# voltage_sensor_v1_2_RJ45.net
KiCad netlist of a schematic drawn in EAGLE
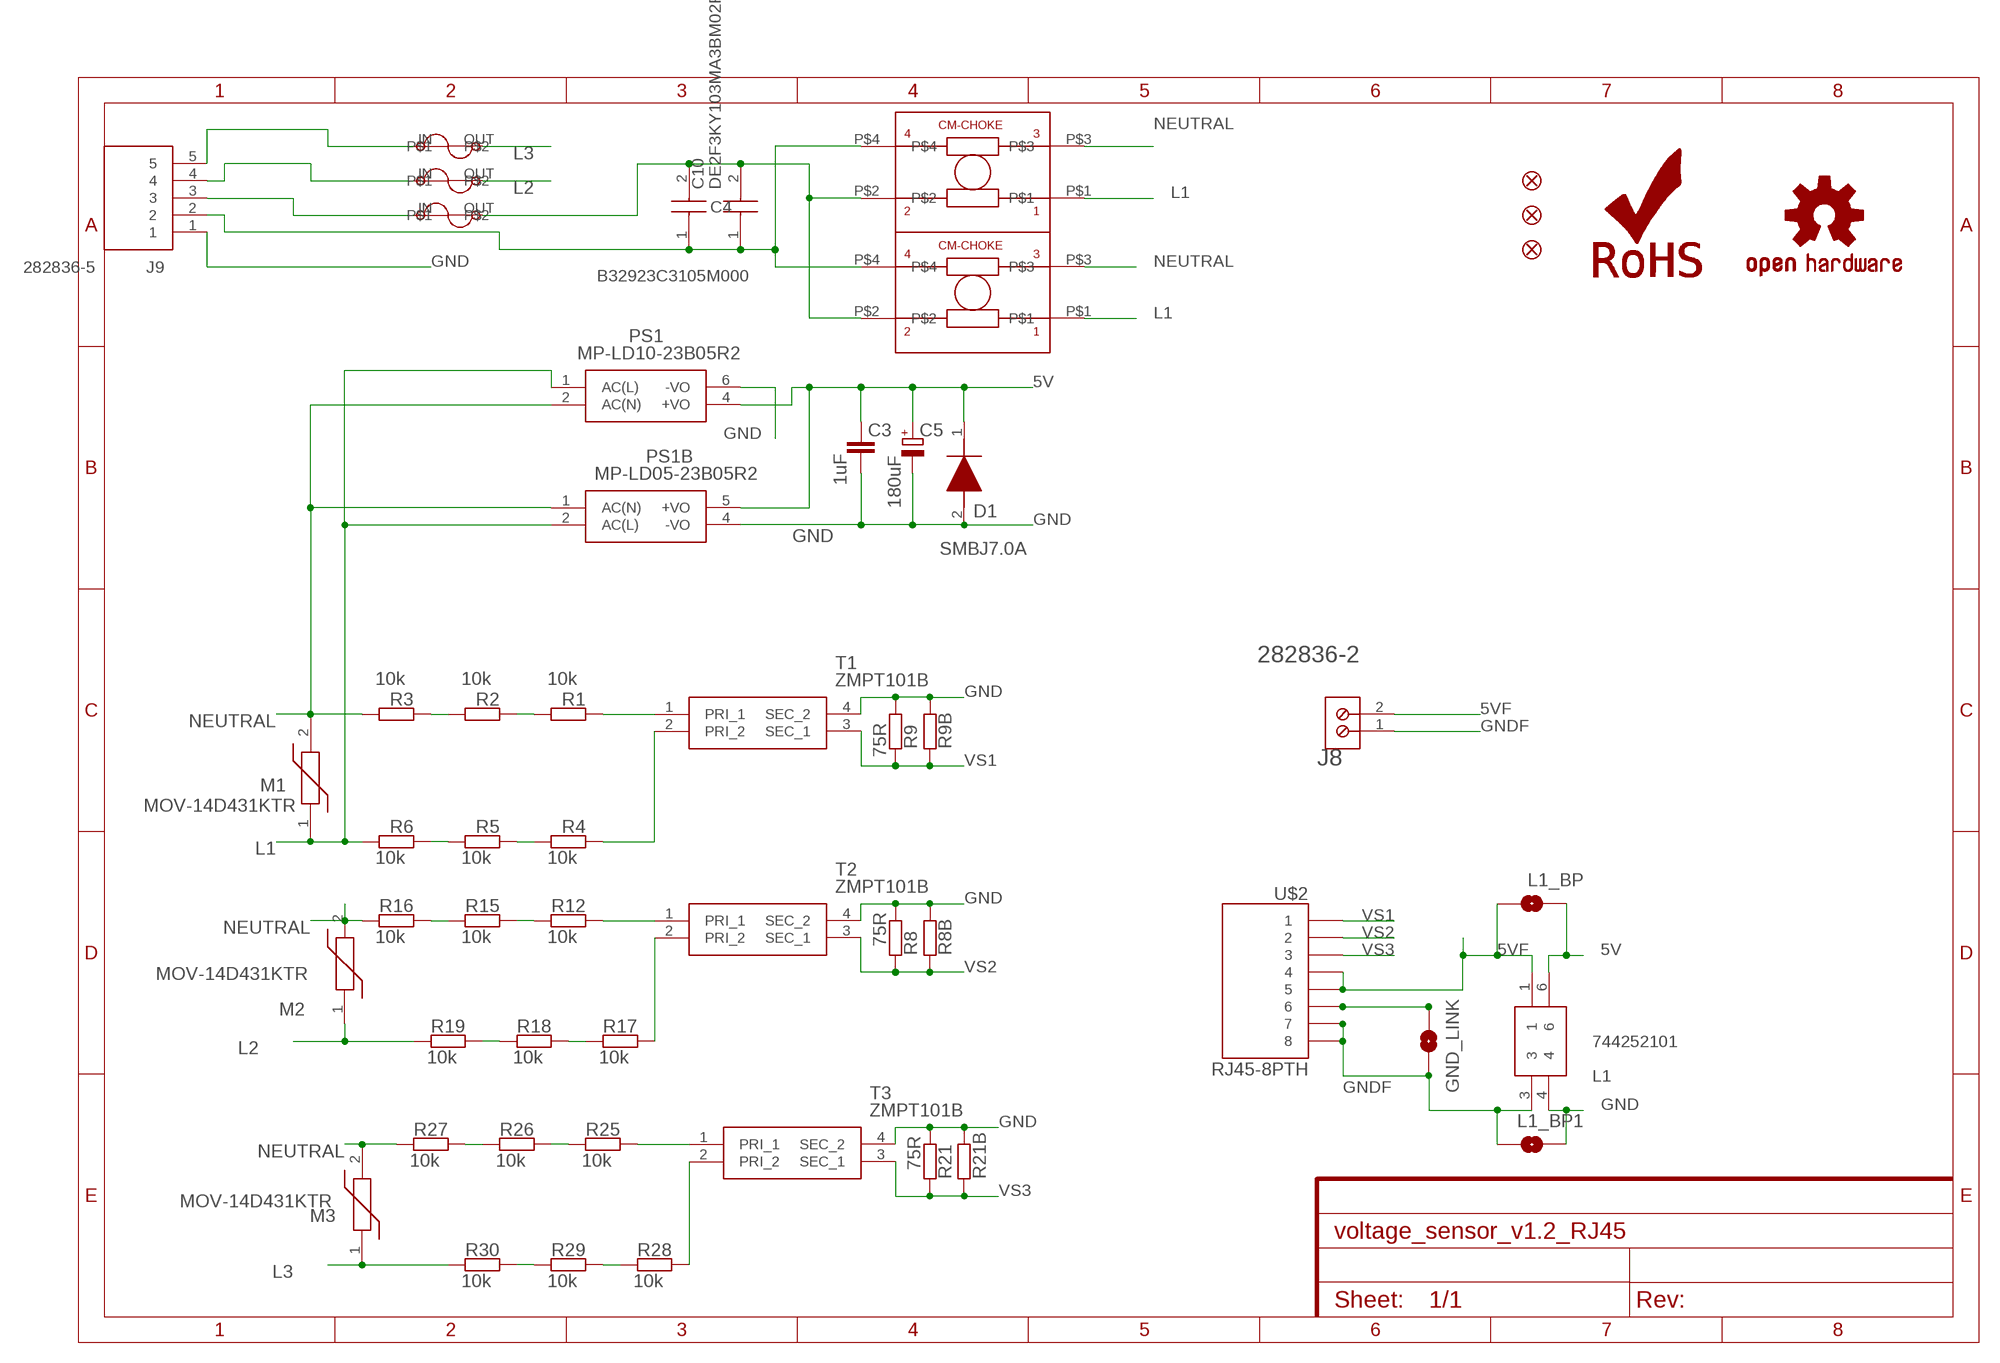
[diagram p0: schematic, sheet 1]

(export (version "E")
  (design (tool "Eeschema 10.0.6"))
  (components
    (comp (ref "C3")
      (value "1uF")
      (footprint "eagle-import:C0603")
      (libsource (lib "eagle-import") (part "C-EUC0603"))
    )
    (comp (ref "C4")
      (value "B32923C3105M000")
      (footprint "eagle-import:B32923C_(26.5_X_12)")
      (libsource (lib "eagle-import") (part "B32923C3105M000"))
    )
    (comp (ref "C5")
      (value "180uF")
      (footprint "eagle-import:PANASONIC_C")
      (libsource (lib "eagle-import") (part "CPOL-EUC"))
    )
    (comp (ref "C10")
      (value "DE2F3KY103MA3BM02F")
      (footprint "eagle-import:DE2F3KY103MA3BM02F")
      (fields (field (name "MOUSER_PART_NUMBER") "81-DE2F3KY103MA3BM2F"))
      (libsource (lib "eagle-import") (part "DE2F3KY103MA3BM02F"))
    )
    (comp (ref "D1")
      (value "SMBJ7.0A")
      (footprint "eagle-import:DIOM5336X244N")
      (libsource (lib "eagle-import") (part "SMBJ7.0A"))
    )
    (comp (ref "F1")
      (value "2A/250V")
      (footprint "eagle-import:BELFUSE1A")
      (libsource (lib "eagle-import") (part "BEL1AFUSE"))
    )
    (comp (ref "F2")
      (value "2A/250V")
      (footprint "eagle-import:BELFUSE1A")
      (libsource (lib "eagle-import") (part "BEL1AFUSE"))
    )
    (comp (ref "F3")
      (value "2A/250V")
      (footprint "eagle-import:BELFUSE1A")
      (libsource (lib "eagle-import") (part "BEL1AFUSE"))
    )
    (comp (ref "FD1")
      (value "FIDUCIAL1X2")
      (footprint "eagle-import:FIDUCIAL-1X2")
      (libsource (lib "eagle-import") (part "FIDUCIAL1X2"))
    )
    (comp (ref "FD2")
      (value "FIDUCIAL1X2")
      (footprint "eagle-import:FIDUCIAL-1X2")
      (libsource (lib "eagle-import") (part "FIDUCIAL1X2"))
    )
    (comp (ref "FD3")
      (value "FIDUCIAL1X2")
      (footprint "eagle-import:FIDUCIAL-1X2")
      (libsource (lib "eagle-import") (part "FIDUCIAL1X2"))
    )
    (comp (ref "GND_LINK")
      (value "SOLDERJUMPERNC")
      (footprint "eagle-import:SJ_2S")
      (libsource (lib "eagle-import") (part "SOLDERJUMPERNC"))
    )
    (comp (ref "J8")
      (value "TE_CONNECTIVITY_282836-2TE_CONNECTIVITY_282836-2_0_0")
      (footprint "eagle-import:TE_CONNECTIVITY_282836-2_0")
      (fields
        (field (name "MF") "TE Connectivity")
        (field (name "MPN") "282836-2")
        (field (name "VOLTAGE") "300V")
      )
      (libsource (lib "eagle-import") (part "TE_CONNECTIVITY_282836-2TE_CONNECTIVITY_282836-2_0_0"))
    )
    (comp (ref "J9")
      (value "282836-5")
      (footprint "eagle-import:2828365")
      (fields (field (name "MOUSER_PART_NUMBER") "571-2828365"))
      (libsource (lib "eagle-import") (part "282836-5"))
    )
    (comp (ref "L1")
      (value "744252101")
      (footprint "eagle-import:744252101")
      (fields (field (name "MOUSER_PART_NUMBER") "710-744252101"))
      (libsource (lib "eagle-import") (part "744252101"))
    )
    (comp (ref "L1_BP")
      (value "SOLDERJUMPERNC")
      (footprint "eagle-import:SJ_2S")
      (libsource (lib "eagle-import") (part "SOLDERJUMPERNC"))
    )
    (comp (ref "L1_BP1")
      (value "SOLDERJUMPERNC")
      (footprint "eagle-import:SJ_2S")
      (libsource (lib "eagle-import") (part "SOLDERJUMPERNC"))
    )
    (comp (ref "LOGO1")
      (value "ROHS_LOGO")
      (footprint "eagle-import:ROHS_LOGO_0.18_IN")
      (libsource (lib "eagle-import") (part "ROHS_LOGO"))
    )
    (comp (ref "LOGO2")
      (value "OSHW-LOGOS-COPPER")
      (footprint "eagle-import:OSHW-LOGO-S_COPPER")
      (libsource (lib "eagle-import") (part "OSHW-LOGOS-COPPER"))
    )
    (comp (ref "M1")
      (value "MOV-14D431KTR")
      (footprint "eagle-import:MOV14D431KTR")
      (fields (field (name "MOUSER_PART_NUMBER") "652-MOV-14D431KTR"))
      (libsource (lib "eagle-import") (part "MOV-14D431KTR"))
    )
    (comp (ref "M2")
      (value "MOV-14D431KTR")
      (footprint "eagle-import:MOV14D431KTR")
      (fields (field (name "MOUSER_PART_NUMBER") "652-MOV-14D431KTR"))
      (libsource (lib "eagle-import") (part "MOV-14D431KTR"))
    )
    (comp (ref "M3")
      (value "MOV-14D431KTR")
      (footprint "eagle-import:MOV14D431KTR")
      (fields (field (name "MOUSER_PART_NUMBER") "652-MOV-14D431KTR"))
      (libsource (lib "eagle-import") (part "MOV-14D431KTR"))
    )
    (comp (ref "PS1")
      (value "MP-LD10-23B05R2")
      (footprint "eagle-import:MPLD1023B12R2")
      (libsource (lib "eagle-import") (part "MP-LD10-23B12R2"))
    )
    (comp (ref "PS1B")
      (value "MP-LD05-23B05R2")
      (footprint "eagle-import:MPLD0523B03R2")
      (fields (field (name "MANUFACTURER_PART_NUMBER") "MP-LD05-23B03R2"))
      (libsource (lib "eagle-import") (part "MP-LD05-23B03R2"))
    )
    (comp (ref "R1")
      (value "10k")
      (footprint "eagle-import:R0603")
      (libsource (lib "eagle-import") (part "R-EU_R0603"))
    )
    (comp (ref "R2")
      (value "10k")
      (footprint "eagle-import:R0603")
      (libsource (lib "eagle-import") (part "R-EU_R0603"))
    )
    (comp (ref "R3")
      (value "10k")
      (footprint "eagle-import:R0603")
      (libsource (lib "eagle-import") (part "R-EU_R0603"))
    )
    (comp (ref "R4")
      (value "10k")
      (footprint "eagle-import:R0603")
      (libsource (lib "eagle-import") (part "R-EU_R0603"))
    )
    (comp (ref "R5")
      (value "10k")
      (footprint "eagle-import:R0603")
      (libsource (lib "eagle-import") (part "R-EU_R0603"))
    )
    (comp (ref "R6")
      (value "10k")
      (footprint "eagle-import:R0603")
      (libsource (lib "eagle-import") (part "R-EU_R0603"))
    )
    (comp (ref "R8")
      (value "75R")
      (footprint "eagle-import:R0603")
      (libsource (lib "eagle-import") (part "R-EU_R0603"))
    )
    (comp (ref "R8B")
      (value "R-EU_0204/7")
      (footprint "eagle-import:0204_7")
      (libsource (lib "eagle-import") (part "R-EU_0204/7"))
    )
    (comp (ref "R9")
      (value "75R")
      (footprint "eagle-import:R0603")
      (libsource (lib "eagle-import") (part "R-EU_R0603"))
    )
    (comp (ref "R9B")
      (value "R-EU_0204/7")
      (footprint "eagle-import:0204_7")
      (libsource (lib "eagle-import") (part "R-EU_0204/7"))
    )
    (comp (ref "R12")
      (value "10k")
      (footprint "eagle-import:R0603")
      (libsource (lib "eagle-import") (part "R-EU_R0603"))
    )
    (comp (ref "R15")
      (value "10k")
      (footprint "eagle-import:R0603")
      (libsource (lib "eagle-import") (part "R-EU_R0603"))
    )
    (comp (ref "R16")
      (value "10k")
      (footprint "eagle-import:R0603")
      (libsource (lib "eagle-import") (part "R-EU_R0603"))
    )
    (comp (ref "R17")
      (value "10k")
      (footprint "eagle-import:R0603")
      (libsource (lib "eagle-import") (part "R-EU_R0603"))
    )
    (comp (ref "R18")
      (value "10k")
      (footprint "eagle-import:R0603")
      (libsource (lib "eagle-import") (part "R-EU_R0603"))
    )
    (comp (ref "R19")
      (value "10k")
      (footprint "eagle-import:R0603")
      (libsource (lib "eagle-import") (part "R-EU_R0603"))
    )
    (comp (ref "R21")
      (value "75R")
      (footprint "eagle-import:R0603")
      (libsource (lib "eagle-import") (part "R-EU_R0603"))
    )
    (comp (ref "R21B")
      (value "R-EU_0204/7")
      (footprint "eagle-import:0204_7")
      (libsource (lib "eagle-import") (part "R-EU_0204/7"))
    )
    (comp (ref "R25")
      (value "10k")
      (footprint "eagle-import:R0603")
      (libsource (lib "eagle-import") (part "R-EU_R0603"))
    )
    (comp (ref "R26")
      (value "10k")
      (footprint "eagle-import:R0603")
      (libsource (lib "eagle-import") (part "R-EU_R0603"))
    )
    (comp (ref "R27")
      (value "10k")
      (footprint "eagle-import:R0603")
      (libsource (lib "eagle-import") (part "R-EU_R0603"))
    )
    (comp (ref "R28")
      (value "10k")
      (footprint "eagle-import:R0603")
      (libsource (lib "eagle-import") (part "R-EU_R0603"))
    )
    (comp (ref "R29")
      (value "10k")
      (footprint "eagle-import:R0603")
      (libsource (lib "eagle-import") (part "R-EU_R0603"))
    )
    (comp (ref "R30")
      (value "10k")
      (footprint "eagle-import:R0603")
      (libsource (lib "eagle-import") (part "R-EU_R0603"))
    )
    (comp (ref "T1")
      (value "ZMPT101B")
      (footprint "eagle-import:ZMPT101B")
      (libsource (lib "eagle-import") (part "ZMPT101B"))
    )
    (comp (ref "T2")
      (value "ZMPT101B")
      (footprint "eagle-import:ZMPT101B")
      (libsource (lib "eagle-import") (part "ZMPT101B"))
    )
    (comp (ref "T3")
      (value "ZMPT101B")
      (footprint "eagle-import:ZMPT101B")
      (libsource (lib "eagle-import") (part "ZMPT101B"))
    )
    (comp (ref "U$1")
      (value "47mH")
      (footprint "eagle-import:RN114-0.3-02-47M")
      (libsource (lib "eagle-import") (part "RN114-0.3-02-47M"))
    )
    (comp (ref "U$1B")
      (value "RN214-0.3-02-47M")
      (footprint "eagle-import:RN214-0.3-02-47M")
      (libsource (lib "eagle-import") (part "RN214-0.3-02-47M"))
    )
    (comp (ref "U$2")
      (value "RJ45-8PTH")
      (footprint "eagle-import:RJ45-8")
      (libsource (lib "eagle-import") (part "RJ45-8PTH"))
    )
  )
  (nets
    (net (code "1") (name "/5V") (class "Default")
      (node (ref "C3") (pin "1") (pinfunction "1_1") (pintype "passive"))
      (node (ref "C5") (pin "+") (pinfunction "+_+") (pintype "passive"))
      (node (ref "D1") (pin "1") (pinfunction "K_1") (pintype "bidirectional"))
      (node (ref "L1") (pin "6") (pinfunction "6_6") (pintype "bidirectional"))
      (node (ref "L1_BP") (pin "1") (pinfunction "1_1") (pintype "passive"))
      (node (ref "PS1") (pin "4") (pinfunction "+VO_4") (pintype "bidirectional"))
      (node (ref "PS1B") (pin "5") (pinfunction "+VO_5") (pintype "bidirectional"))
    )
    (net (code "2") (name "/5VF") (class "Default")
      (node (ref "J8") (pin "2") (pinfunction "2_2") (pintype "passive"))
      (node (ref "L1") (pin "1") (pinfunction "1_1") (pintype "bidirectional"))
      (node (ref "L1_BP") (pin "2") (pinfunction "2_2") (pintype "passive"))
      (node (ref "U$2") (pin "4") (pinfunction "4_4") (pintype "bidirectional"))
      (node (ref "U$2") (pin "5") (pinfunction "5_5") (pintype "bidirectional"))
    )
    (net (code "3") (name "/GND") (class "Default")
      (node (ref "C3") (pin "2") (pinfunction "2_2") (pintype "passive"))
      (node (ref "C5") (pin "-") (pinfunction "-_-") (pintype "passive"))
      (node (ref "D1") (pin "2") (pinfunction "A_2") (pintype "bidirectional"))
      (node (ref "J9") (pin "1") (pinfunction "1_1") (pintype "bidirectional"))
      (node (ref "L1") (pin "4") (pinfunction "4_4") (pintype "bidirectional"))
      (node (ref "L1_BP1") (pin "1") (pinfunction "1_1") (pintype "passive"))
      (node (ref "PS1") (pin "6") (pinfunction "-VO_6") (pintype "bidirectional"))
      (node (ref "PS1B") (pin "4") (pinfunction "-VO_4") (pintype "bidirectional"))
      (node (ref "R21") (pin "2") (pinfunction "2_2") (pintype "passive"))
      (node (ref "R21B") (pin "2") (pinfunction "2_2") (pintype "passive"))
      (node (ref "R8") (pin "2") (pinfunction "2_2") (pintype "passive"))
      (node (ref "R8B") (pin "2") (pinfunction "2_2") (pintype "passive"))
      (node (ref "R9") (pin "2") (pinfunction "2_2") (pintype "passive"))
      (node (ref "R9B") (pin "2") (pinfunction "2_2") (pintype "passive"))
      (node (ref "T1") (pin "4") (pinfunction "SEC_2_4") (pintype "bidirectional"))
      (node (ref "T2") (pin "4") (pinfunction "SEC_2_4") (pintype "bidirectional"))
      (node (ref "T3") (pin "4") (pinfunction "SEC_2_4") (pintype "bidirectional"))
    )
    (net (code "4") (name "/GNDF") (class "Default")
      (node (ref "GND_LINK") (pin "1") (pinfunction "1_1") (pintype "passive"))
      (node (ref "J8") (pin "1") (pinfunction "1_1") (pintype "passive"))
      (node (ref "L1") (pin "3") (pinfunction "3_3") (pintype "bidirectional"))
      (node (ref "L1_BP1") (pin "2") (pinfunction "2_2") (pintype "passive"))
      (node (ref "U$2") (pin "7") (pinfunction "7_7") (pintype "bidirectional"))
      (node (ref "U$2") (pin "8") (pinfunction "8_8") (pintype "bidirectional"))
    )
    (net (code "5") (name "/L1") (class "Default")
      (node (ref "M1") (pin "1") (pinfunction "1_1") (pintype "bidirectional"))
      (node (ref "PS1") (pin "1") (pinfunction "AC(L)_1") (pintype "bidirectional"))
      (node (ref "PS1B") (pin "2") (pinfunction "AC(L)_2") (pintype "bidirectional"))
      (node (ref "R6") (pin "2") (pinfunction "2_2") (pintype "passive"))
      (node (ref "U$1") (pin "P$1") (pinfunction "P$1_P$1") (pintype "bidirectional"))
      (node (ref "U$1B") (pin "P$1") (pinfunction "P$1_P$1") (pintype "bidirectional"))
    )
    (net (code "6") (name "/L2") (class "Default")
      (node (ref "F2") (pin "OUT") (pinfunction "P$1_OUT") (pintype "bidirectional"))
      (node (ref "M2") (pin "1") (pinfunction "1_1") (pintype "bidirectional"))
      (node (ref "R19") (pin "2") (pinfunction "2_2") (pintype "passive"))
    )
    (net (code "7") (name "/L3") (class "Default")
      (node (ref "F3") (pin "OUT") (pinfunction "P$1_OUT") (pintype "bidirectional"))
      (node (ref "M3") (pin "1") (pinfunction "1_1") (pintype "bidirectional"))
      (node (ref "R30") (pin "2") (pinfunction "2_2") (pintype "passive"))
    )
    (net (code "8") (name "/NEUTRAL") (class "Default")
      (node (ref "M1") (pin "2") (pinfunction "2_2") (pintype "bidirectional"))
      (node (ref "M2") (pin "2") (pinfunction "2_2") (pintype "bidirectional"))
      (node (ref "M3") (pin "2") (pinfunction "2_2") (pintype "bidirectional"))
      (node (ref "PS1") (pin "2") (pinfunction "AC(N)_2") (pintype "bidirectional"))
      (node (ref "PS1B") (pin "1") (pinfunction "AC(N)_1") (pintype "bidirectional"))
      (node (ref "R16") (pin "2") (pinfunction "2_2") (pintype "passive"))
      (node (ref "R27") (pin "2") (pinfunction "2_2") (pintype "passive"))
      (node (ref "R3") (pin "2") (pinfunction "2_2") (pintype "passive"))
      (node (ref "U$1") (pin "P$3") (pinfunction "P$3_P$3") (pintype "bidirectional"))
      (node (ref "U$1B") (pin "P$3") (pinfunction "P$3_P$3") (pintype "bidirectional"))
    )
    (net (code "9") (name "/VS1") (class "Default")
      (node (ref "R9") (pin "1") (pinfunction "1_1") (pintype "passive"))
      (node (ref "R9B") (pin "1") (pinfunction "1_1") (pintype "passive"))
      (node (ref "T1") (pin "3") (pinfunction "SEC_1_3") (pintype "bidirectional"))
      (node (ref "U$2") (pin "1") (pinfunction "1_1") (pintype "bidirectional"))
    )
    (net (code "10") (name "/VS2") (class "Default")
      (node (ref "R8") (pin "1") (pinfunction "1_1") (pintype "passive"))
      (node (ref "R8B") (pin "1") (pinfunction "1_1") (pintype "passive"))
      (node (ref "T2") (pin "3") (pinfunction "SEC_1_3") (pintype "bidirectional"))
      (node (ref "U$2") (pin "2") (pinfunction "2_2") (pintype "bidirectional"))
    )
    (net (code "11") (name "/VS3") (class "Default")
      (node (ref "R21") (pin "1") (pinfunction "1_1") (pintype "passive"))
      (node (ref "R21B") (pin "1") (pinfunction "1_1") (pintype "passive"))
      (node (ref "T3") (pin "3") (pinfunction "SEC_1_3") (pintype "bidirectional"))
      (node (ref "U$2") (pin "3") (pinfunction "3_3") (pintype "bidirectional"))
    )
    (net (code "12") (name "Net-(C10-Pad1)") (class "Default")
      (node (ref "C10") (pin "1") (pinfunction "1_1") (pintype "bidirectional"))
      (node (ref "C4") (pin "1") (pinfunction "1_1") (pintype "bidirectional"))
      (node (ref "J9") (pin "2") (pinfunction "2_2") (pintype "bidirectional"))
      (node (ref "U$1") (pin "P$4") (pinfunction "P$4_P$4") (pintype "bidirectional"))
      (node (ref "U$1B") (pin "P$4") (pinfunction "P$4_P$4") (pintype "bidirectional"))
    )
    (net (code "13") (name "Net-(F1-P$1)") (class "Default")
      (node (ref "C10") (pin "2") (pinfunction "2_2") (pintype "bidirectional"))
      (node (ref "C4") (pin "2") (pinfunction "2_2") (pintype "bidirectional"))
      (node (ref "F1") (pin "OUT") (pinfunction "P$1_OUT") (pintype "bidirectional"))
      (node (ref "U$1") (pin "P$2") (pinfunction "P$2_P$2") (pintype "bidirectional"))
      (node (ref "U$1B") (pin "P$2") (pinfunction "P$2_P$2") (pintype "bidirectional"))
    )
    (net (code "14") (name "Net-(F1-P$2)") (class "Default")
      (node (ref "F1") (pin "IN") (pinfunction "P$2_IN") (pintype "bidirectional"))
      (node (ref "J9") (pin "3") (pinfunction "3_3") (pintype "bidirectional"))
    )
    (net (code "15") (name "Net-(F2-P$2)") (class "Default")
      (node (ref "F2") (pin "IN") (pinfunction "P$2_IN") (pintype "bidirectional"))
      (node (ref "J9") (pin "4") (pinfunction "4_4") (pintype "bidirectional"))
    )
    (net (code "16") (name "Net-(F3-P$2)") (class "Default")
      (node (ref "F3") (pin "IN") (pinfunction "P$2_IN") (pintype "bidirectional"))
      (node (ref "J9") (pin "5") (pinfunction "5_5") (pintype "bidirectional"))
    )
    (net (code "17") (name "Net-(GND_LINK-Pad2)") (class "Default")
      (node (ref "GND_LINK") (pin "2") (pinfunction "2_2") (pintype "passive"))
      (node (ref "U$2") (pin "6") (pinfunction "6_6") (pintype "bidirectional"))
    )
    (net (code "18") (name "Net-(R1-Pad2)") (class "Default")
      (node (ref "R1") (pin "2") (pinfunction "2_2") (pintype "passive"))
      (node (ref "R2") (pin "1") (pinfunction "1_1") (pintype "passive"))
    )
    (net (code "19") (name "Net-(R2-Pad2)") (class "Default")
      (node (ref "R2") (pin "2") (pinfunction "2_2") (pintype "passive"))
      (node (ref "R3") (pin "1") (pinfunction "1_1") (pintype "passive"))
    )
    (net (code "20") (name "Net-(R4-Pad2)") (class "Default")
      (node (ref "R4") (pin "2") (pinfunction "2_2") (pintype "passive"))
      (node (ref "R5") (pin "1") (pinfunction "1_1") (pintype "passive"))
    )
    (net (code "21") (name "Net-(R5-Pad2)") (class "Default")
      (node (ref "R5") (pin "2") (pinfunction "2_2") (pintype "passive"))
      (node (ref "R6") (pin "1") (pinfunction "1_1") (pintype "passive"))
    )
    (net (code "22") (name "Net-(R12-Pad2)") (class "Default")
      (node (ref "R12") (pin "2") (pinfunction "2_2") (pintype "passive"))
      (node (ref "R15") (pin "1") (pinfunction "1_1") (pintype "passive"))
    )
    (net (code "23") (name "Net-(R15-Pad2)") (class "Default")
      (node (ref "R15") (pin "2") (pinfunction "2_2") (pintype "passive"))
      (node (ref "R16") (pin "1") (pinfunction "1_1") (pintype "passive"))
    )
    (net (code "24") (name "Net-(R17-Pad2)") (class "Default")
      (node (ref "R17") (pin "2") (pinfunction "2_2") (pintype "passive"))
      (node (ref "R18") (pin "1") (pinfunction "1_1") (pintype "passive"))
    )
    (net (code "25") (name "Net-(R18-Pad2)") (class "Default")
      (node (ref "R18") (pin "2") (pinfunction "2_2") (pintype "passive"))
      (node (ref "R19") (pin "1") (pinfunction "1_1") (pintype "passive"))
    )
    (net (code "26") (name "Net-(R25-Pad2)") (class "Default")
      (node (ref "R25") (pin "2") (pinfunction "2_2") (pintype "passive"))
      (node (ref "R26") (pin "1") (pinfunction "1_1") (pintype "passive"))
    )
    (net (code "27") (name "Net-(R26-Pad2)") (class "Default")
      (node (ref "R26") (pin "2") (pinfunction "2_2") (pintype "passive"))
      (node (ref "R27") (pin "1") (pinfunction "1_1") (pintype "passive"))
    )
    (net (code "28") (name "Net-(R28-Pad2)") (class "Default")
      (node (ref "R28") (pin "2") (pinfunction "2_2") (pintype "passive"))
      (node (ref "R29") (pin "1") (pinfunction "1_1") (pintype "passive"))
    )
    (net (code "29") (name "Net-(R29-Pad2)") (class "Default")
      (node (ref "R29") (pin "2") (pinfunction "2_2") (pintype "passive"))
      (node (ref "R30") (pin "1") (pinfunction "1_1") (pintype "passive"))
    )
    (net (code "30") (name "Net-(T1-PRI_1)") (class "Default")
      (node (ref "R1") (pin "1") (pinfunction "1_1") (pintype "passive"))
      (node (ref "T1") (pin "1") (pinfunction "PRI_1_1") (pintype "bidirectional"))
    )
    (net (code "31") (name "Net-(T1-PRI_2)") (class "Default")
      (node (ref "R4") (pin "1") (pinfunction "1_1") (pintype "passive"))
      (node (ref "T1") (pin "2") (pinfunction "PRI_2_2") (pintype "bidirectional"))
    )
    (net (code "32") (name "Net-(T2-PRI_1)") (class "Default")
      (node (ref "R12") (pin "1") (pinfunction "1_1") (pintype "passive"))
      (node (ref "T2") (pin "1") (pinfunction "PRI_1_1") (pintype "bidirectional"))
    )
    (net (code "33") (name "Net-(T2-PRI_2)") (class "Default")
      (node (ref "R17") (pin "1") (pinfunction "1_1") (pintype "passive"))
      (node (ref "T2") (pin "2") (pinfunction "PRI_2_2") (pintype "bidirectional"))
    )
    (net (code "34") (name "Net-(T3-PRI_1)") (class "Default")
      (node (ref "R25") (pin "1") (pinfunction "1_1") (pintype "passive"))
      (node (ref "T3") (pin "1") (pinfunction "PRI_1_1") (pintype "bidirectional"))
    )
    (net (code "35") (name "Net-(T3-PRI_2)") (class "Default")
      (node (ref "R28") (pin "1") (pinfunction "1_1") (pintype "passive"))
      (node (ref "T3") (pin "2") (pinfunction "PRI_2_2") (pintype "bidirectional"))
    )
  )
)
